# MCU.net
KiCad netlist of a schematic drawn in Altium Designer
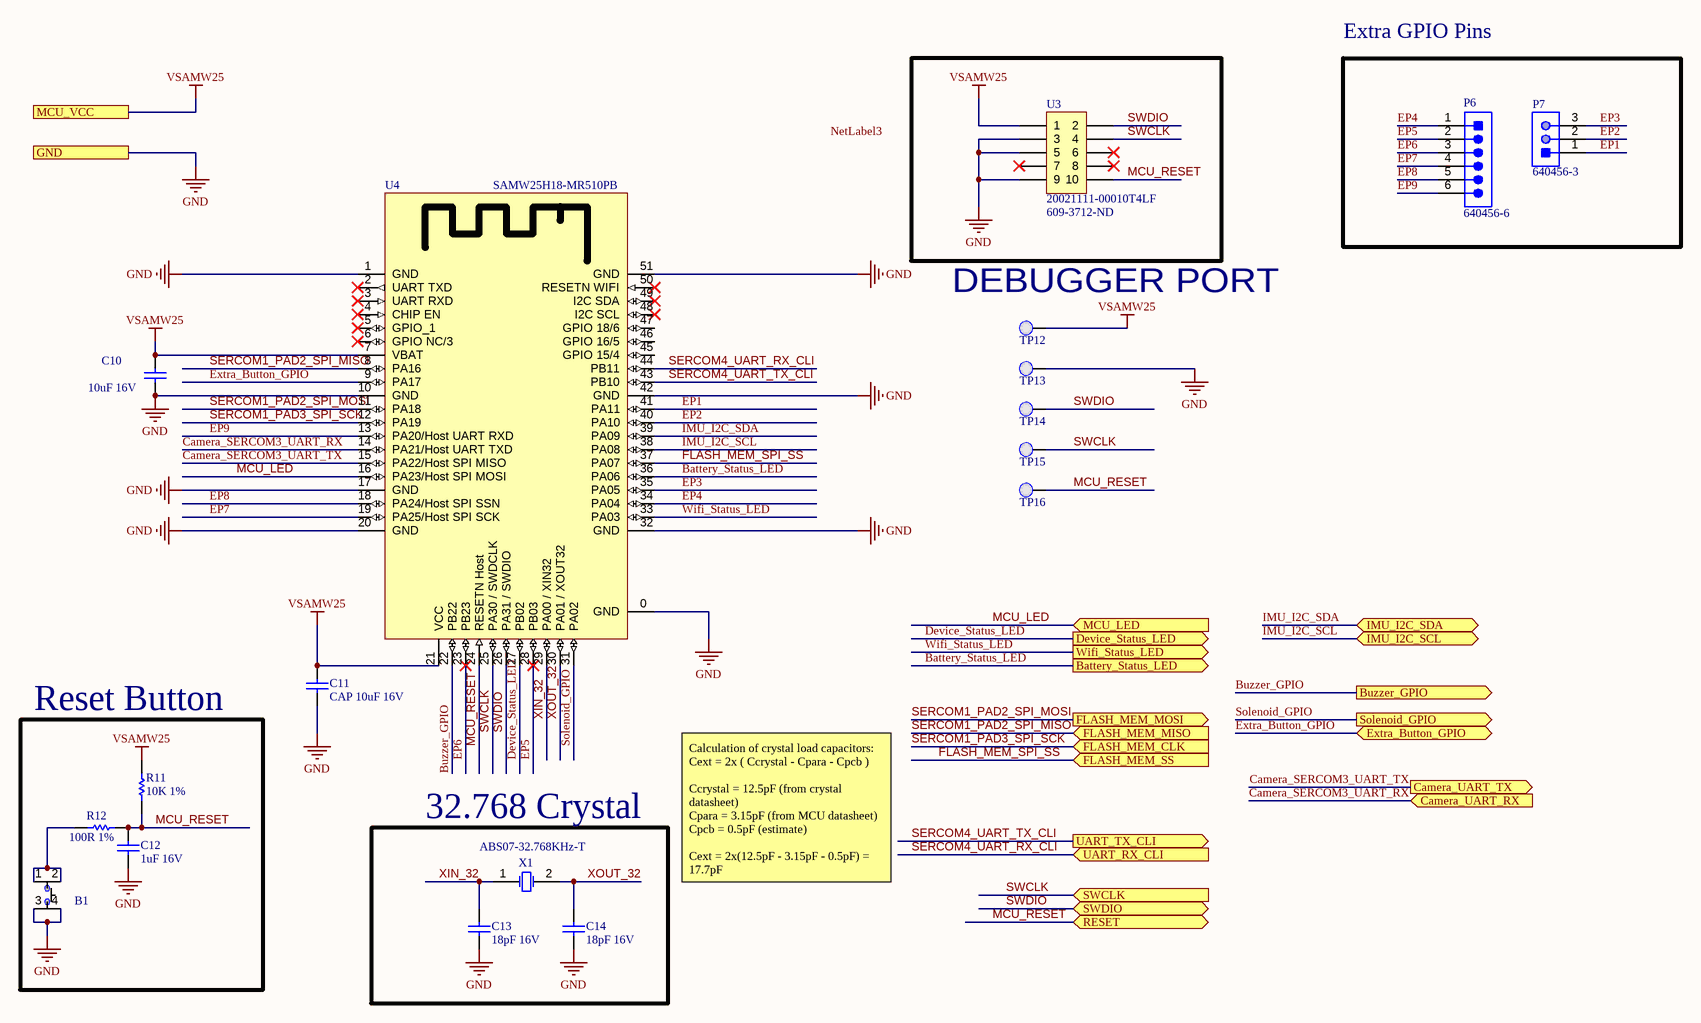
[diagram p0: MCU.SchDoc]

(export (version "E")
  (design (tool "Eeschema 10.0.6"))
  (components
    (comp (ref "B1")
      (value "PTS810 SJK 250 SMTR LFS")
      (footprint "PTS810 SJK 250 SMTR LFS")
      (description "SWITCH TACTILE SPST-NO 0.05A 16V Tactile Switch SPST-NO Top Actuated Surface Mount")
      (fields
        (field (name "MANUFACTURER") "ITT /  C&K Components")
        (field (name "MANUFACTURER PART NUMBER") "PTS810SJK250SMTRLFS")
      )
      (libsource (lib "Schematics") (part "PTS810 SJK 250 SMTR LFS"))
    )
    (comp (ref "C10")
      (value "10uF 16V")
      (footprint "CAPC0805(2012)145_N")
      (description "CAP 10uF 16V ±10% 0805 (2012 Metric) Thickness 1.45mm SMD")
      (fields (field (name "TOLERANCE") "Â±10%"))
      (libsource (lib "Altium Content Vault") (part "CAP"))
    )
    (comp (ref "C11")
      (value "CAP 10uF 16V")
      (footprint "CAPC0805(2012)145_N")
      (description "CAP 10uF 16V ±10% 0805 (2012 Metric) Thickness 1.45mm SMD")
      (fields (field (name "TOLERANCE") "Â±10%"))
      (libsource (lib "Altium Content Vault") (part "CAP"))
    )
    (comp (ref "C12")
      (value "1uF 16V")
      (footprint "CAPC0603(1608)100_N")
      (description "CAP 1uF 16V ±5% 0603 (1608 Metric) Thickness 1mm SMD")
      (fields (field (name "TOLERANCE") "Â±5%"))
      (libsource (lib "Altium Content Vault") (part "CAP"))
    )
    (comp (ref "C13")
      (value "18pF 16V")
      (footprint "CAPC0603(1608)100_N")
      (description "CAP 18pF 16V ±5% 0603 (1608 Metric) Thickness 1mm SMD")
      (fields (field (name "TOLERANCE") "Â±5%"))
      (libsource (lib "Altium Content Vault") (part "CAP"))
    )
    (comp (ref "C14")
      (value "18pF 16V")
      (footprint "CAPC0603(1608)100_N")
      (description "CAP 18pF 16V ±5% 0603 (1608 Metric) Thickness 1mm SMD")
      (fields (field (name "TOLERANCE") "Â±5%"))
      (libsource (lib "Altium Content Vault") (part "CAP"))
    )
    (comp (ref "P6")
      (value "640456-6")
      (footprint "TECO-640456-6_V")
      (fields (field (name "MANUFACTURER") "TE Connectivity"))
      (libsource (lib "Altium Content Vault") (part "CN-1P-M-R6"))
    )
    (comp (ref "P7")
      (value "640456-3")
      (footprint "TECO-640456-3")
      (description "Male Header, Pitch 2.54 mm, 1 x 3 Position, Height 10.03 mm, Tail Length 3.56 mm, -55 to 105 degC")
      (fields (field (name "MANUFACTURER") "TE Connectivity"))
      (libsource (lib "Altium Content Vault") (part "CN-1P-M-R3"))
    )
    (comp (ref "R11")
      (value "10K 1%")
      (footprint "RESC0603(1608)_N")
      (description "10K 0.1W 1% 0603 (1608 Metric)  SMD")
      (fields (field (name "POWER") "0.1 W") (field (name "TOLERANCE") "1 %"))
      (libsource (lib "Altium Content Vault") (part "RES"))
    )
    (comp (ref "R12")
      (value "100R 1%")
      (footprint "RESC0603(1608)_N")
      (description "100R 0.1W 1% 0603 (1608 Metric)  SMD")
      (fields (field (name "TOLERANCE") "1 %") (field (name "POWER") "0.1 W"))
      (libsource (lib "Altium Content Vault") (part "RES"))
    )
    (comp (ref "TP12")
      (value "0.1\" Pad")
      (footprint "PCBComponent")
      (libsource (lib "Components - 12.02.20 - 18.05") (part "0.1{dblquote} Pad-A.4"))
    )
    (comp (ref "TP13")
      (value "0.1\" Pad")
      (footprint "PCBComponent")
      (libsource (lib "Components - 12.02.20 - 18.05") (part "0.1{dblquote} Pad-A.4"))
    )
    (comp (ref "TP14")
      (value "0.1\" Pad")
      (footprint "PCBComponent")
      (libsource (lib "Components - 12.02.20 - 18.05") (part "0.1{dblquote} Pad-A.4"))
    )
    (comp (ref "TP15")
      (value "0.1\" Pad")
      (footprint "PCBComponent")
      (libsource (lib "Components - 12.02.20 - 18.05") (part "0.1{dblquote} Pad-A.4"))
    )
    (comp (ref "TP16")
      (value "0.1\" Pad")
      (footprint "PCBComponent")
      (libsource (lib "Components - 12.02.20 - 18.05") (part "0.1{dblquote} Pad-A.4"))
    )
    (comp (ref "U3")
      (value "20021111-00010T4LF")
      (footprint "20021111-00010T4LF")
      (description "CONN HEADER 10POS UNSHD VERT T/H")
      (fields
        (field (name "MANUFACTURER") "Amphenol / FCI")
        (field (name "SUPPLIER PART NUMBER 1") "609-3712-ND")
      )
      (libsource (lib "Schematics") (part "20021111-00010T4LF"))
    )
    (comp (ref "U4")
      (value "SAMW25H18-MR510PB")
      (footprint "SAMW25H18-MR510PB")
      (description "RF TXRX MODULE WIFI TRACE ANT")
      (fields
        (field (name "MANUFACTURER") "Atmel")
        (field (name "MANUFACTURER PART NUMBER") "ATSAMW25H18-MR510PB")
      )
      (libsource (lib "Schematics") (part "SAMW25H18-MR510PB"))
    )
    (comp (ref "X1")
      (value "ABS07-32.768KHz-T")
      (footprint "ABRA-ABS07-2_V")
      (description "Crystal, 32.768 kHz, 12.5 pF, -40 to 85 degC, SMD Low Profile 3.2 x 1.5 x 0.9 mm, Tape and Reel")
      (fields (field (name "MANUFACTURER") "Abracon"))
      (libsource (lib "Altium Content Vault") (part "ABRA-ABS07-2"))
    )
  )
  (nets
    (net (code "1") (name "/Battery_Status_LED") (class "Default")
      (node (ref "U4") (pin "36") (pinfunction "PA06_36") (pintype "bidirectional"))
    )
    (net (code "2") (name "/Buzzer_GPIO") (class "Default")
      (node (ref "U4") (pin "22") (pinfunction "PB22_22") (pintype "bidirectional"))
    )
    (net (code "3") (name "/Camera_SERCOM3_UART_RX") (class "Default")
      (node (ref "U4") (pin "14") (pinfunction "PA21/Host_UART_TXD_14") (pintype "bidirectional"))
    )
    (net (code "4") (name "/Camera_SERCOM3_UART_TX") (class "Default")
      (node (ref "U4") (pin "15") (pinfunction "PA22/Host_SPI_MISO_15") (pintype "bidirectional"))
    )
    (net (code "5") (name "/Device_Status_LED") (class "Default")
      (node (ref "U4") (pin "27") (pinfunction "PB02_27") (pintype "bidirectional"))
    )
    (net (code "6") (name "/EP1") (class "Default")
      (node (ref "P7") (pin "1") (pinfunction "1_1") (pintype "passive"))
      (node (ref "U4") (pin "41") (pinfunction "PA11_41") (pintype "bidirectional"))
    )
    (net (code "7") (name "/EP2") (class "Default")
      (node (ref "P7") (pin "2") (pinfunction "2_2") (pintype "passive"))
      (node (ref "U4") (pin "40") (pinfunction "PA10_40") (pintype "bidirectional"))
    )
    (net (code "8") (name "/EP3") (class "Default")
      (node (ref "P7") (pin "3") (pinfunction "3_3") (pintype "passive"))
      (node (ref "U4") (pin "35") (pinfunction "PA05_35") (pintype "bidirectional"))
    )
    (net (code "9") (name "/EP4") (class "Default")
      (node (ref "P6") (pin "1") (pinfunction "1_1") (pintype "passive"))
      (node (ref "U4") (pin "34") (pinfunction "PA04_34") (pintype "bidirectional"))
    )
    (net (code "10") (name "/EP5") (class "Default")
      (node (ref "P6") (pin "2") (pinfunction "2_2") (pintype "passive"))
      (node (ref "U4") (pin "28") (pinfunction "PB03_28") (pintype "bidirectional"))
    )
    (net (code "11") (name "/EP6") (class "Default")
      (node (ref "P6") (pin "3") (pinfunction "3_3") (pintype "passive"))
      (node (ref "U4") (pin "23") (pinfunction "PB23_23") (pintype "bidirectional"))
    )
    (net (code "12") (name "/EP7") (class "Default")
      (node (ref "P6") (pin "4") (pinfunction "4_4") (pintype "passive"))
      (node (ref "U4") (pin "19") (pinfunction "PA25/Host_SPI_SCK_19") (pintype "bidirectional"))
    )
    (net (code "13") (name "/EP8") (class "Default")
      (node (ref "P6") (pin "5") (pinfunction "5_5") (pintype "passive"))
      (node (ref "U4") (pin "18") (pinfunction "PA24/Host_SPI_SSN_18") (pintype "bidirectional"))
    )
    (net (code "14") (name "/EP9") (class "Default")
      (node (ref "P6") (pin "6") (pinfunction "6_6") (pintype "passive"))
      (node (ref "U4") (pin "13") (pinfunction "PA20/Host_UART_RXD_13") (pintype "bidirectional"))
    )
    (net (code "15") (name "/Extra_Button_GPIO") (class "Default")
      (node (ref "U4") (pin "9") (pinfunction "PA17_9") (pintype "bidirectional"))
    )
    (net (code "16") (name "/FLASH_MEM_SPI_SS") (class "Default")
      (node (ref "U4") (pin "37") (pinfunction "PA07_37") (pintype "bidirectional"))
    )
    (net (code "17") (name "/IMU_I2C_SCL") (class "Default")
      (node (ref "U4") (pin "38") (pinfunction "PA08_38") (pintype "bidirectional"))
    )
    (net (code "18") (name "/IMU_I2C_SDA") (class "Default")
      (node (ref "U4") (pin "39") (pinfunction "PA09_39") (pintype "bidirectional"))
    )
    (net (code "19") (name "/MCU_LED") (class "Default")
      (node (ref "U4") (pin "16") (pinfunction "PA23/Host_SPI_MOSI_16") (pintype "bidirectional"))
    )
    (net (code "20") (name "/MCU_RESET") (class "Default")
      (node (ref "C12") (pin "2") (pinfunction "2_2") (pintype "passive"))
      (node (ref "R11") (pin "1") (pinfunction "1_1") (pintype "passive"))
      (node (ref "R12") (pin "2") (pinfunction "2_2") (pintype "passive"))
      (node (ref "TP16") (pin "1") (pinfunction "PAD_1") (pintype "passive"))
      (node (ref "U3") (pin "10") (pinfunction "10_10") (pintype "passive"))
      (node (ref "U4") (pin "24") (pinfunction "RESETN_Host_24") (pintype "input"))
    )
    (net (code "22") (name "/SERCOM1_PAD2_SPI_MISO") (class "Default")
      (node (ref "U4") (pin "8") (pinfunction "PA16_8") (pintype "bidirectional"))
    )
    (net (code "23") (name "/SERCOM1_PAD2_SPI_MOSI") (class "Default")
      (node (ref "U4") (pin "11") (pinfunction "PA18_11") (pintype "bidirectional"))
    )
    (net (code "24") (name "/SERCOM1_PAD3_SPI_SCK") (class "Default")
      (node (ref "U4") (pin "12") (pinfunction "PA19_12") (pintype "bidirectional"))
    )
    (net (code "25") (name "/SERCOM4_UART_RX_CLI") (class "Default")
      (node (ref "U4") (pin "44") (pinfunction "PB11_44") (pintype "bidirectional"))
    )
    (net (code "26") (name "/SERCOM4_UART_TX_CLI") (class "Default")
      (node (ref "U4") (pin "43") (pinfunction "PB10_43") (pintype "bidirectional"))
    )
    (net (code "27") (name "/SWCLK") (class "Default")
      (node (ref "TP15") (pin "1") (pinfunction "PAD_1") (pintype "passive"))
      (node (ref "U3") (pin "4") (pinfunction "4_4") (pintype "passive"))
      (node (ref "U4") (pin "25") (pinfunction "PA30_/_SWDCLK_25") (pintype "bidirectional"))
    )
    (net (code "28") (name "/SWDIO") (class "Default")
      (node (ref "TP14") (pin "1") (pinfunction "PAD_1") (pintype "passive"))
      (node (ref "U3") (pin "2") (pinfunction "2_2") (pintype "passive"))
      (node (ref "U4") (pin "26") (pinfunction "PA31_/_SWDIO_26") (pintype "bidirectional"))
    )
    (net (code "29") (name "/Solenoid_GPIO") (class "Default")
      (node (ref "U4") (pin "31") (pinfunction "PA02_31") (pintype "bidirectional"))
    )
    (net (code "30") (name "/Wifi_Status_LED") (class "Default")
      (node (ref "U4") (pin "33") (pinfunction "PA03_33") (pintype "bidirectional"))
    )
    (net (code "31") (name "/XIN_32") (class "Default")
      (node (ref "C13") (pin "2") (pinfunction "2_2") (pintype "passive"))
      (node (ref "U4") (pin "29") (pinfunction "PA00_/_XIN32_29") (pintype "bidirectional"))
      (node (ref "X1") (pin "1") (pinfunction "X1_1") (pintype "passive"))
    )
    (net (code "32") (name "/XOUT_32") (class "Default")
      (node (ref "C14") (pin "2") (pinfunction "2_2") (pintype "passive"))
      (node (ref "U4") (pin "30") (pinfunction "PA01_/_XOUT32_30") (pintype "bidirectional"))
      (node (ref "X1") (pin "2") (pinfunction "X2_2") (pintype "passive"))
    )
    (net (code "33") (name "GND") (class "Default")
      (node (ref "B1") (pin "3") (pinfunction "3_3") (pintype "power_in"))
      (node (ref "B1") (pin "4") (pinfunction "4_4") (pintype "power_in"))
      (node (ref "C10") (pin "1") (pinfunction "1_1") (pintype "passive"))
      (node (ref "C11") (pin "1") (pinfunction "1_1") (pintype "passive"))
      (node (ref "C12") (pin "1") (pinfunction "1_1") (pintype "passive"))
      (node (ref "C13") (pin "1") (pinfunction "1_1") (pintype "passive"))
      (node (ref "C14") (pin "1") (pinfunction "1_1") (pintype "passive"))
      (node (ref "TP13") (pin "1") (pinfunction "PAD_1") (pintype "passive"))
      (node (ref "U3") (pin "3") (pinfunction "3_3") (pintype "passive"))
      (node (ref "U3") (pin "5") (pinfunction "5_5") (pintype "passive"))
      (node (ref "U3") (pin "9") (pinfunction "9_9") (pintype "passive"))
      (node (ref "U4") (pin "0") (pinfunction "GND_0") (pintype "power_in"))
      (node (ref "U4") (pin "1") (pinfunction "GND_1") (pintype "power_in"))
      (node (ref "U4") (pin "10") (pinfunction "GND_10") (pintype "power_in"))
      (node (ref "U4") (pin "17") (pinfunction "GND_17") (pintype "power_in"))
      (node (ref "U4") (pin "20") (pinfunction "GND_20") (pintype "power_in"))
      (node (ref "U4") (pin "32") (pinfunction "GND_32") (pintype "power_in"))
      (node (ref "U4") (pin "42") (pinfunction "GND_42") (pintype "power_in"))
      (node (ref "U4") (pin "51") (pinfunction "GND_51") (pintype "power_in"))
    )
    (net (code "34") (name "Net-(B1-Pad1)") (class "Default")
      (node (ref "B1") (pin "1") (pinfunction "1_1") (pintype "power_in"))
      (node (ref "B1") (pin "2") (pinfunction "2_2") (pintype "power_in"))
      (node (ref "R12") (pin "1") (pinfunction "1_1") (pintype "passive"))
    )
    (net (code "35") (name "VSAMW25") (class "Default")
      (node (ref "C10") (pin "2") (pinfunction "2_2") (pintype "passive"))
      (node (ref "C11") (pin "2") (pinfunction "2_2") (pintype "passive"))
      (node (ref "R11") (pin "2") (pinfunction "2_2") (pintype "passive"))
      (node (ref "TP12") (pin "1") (pinfunction "PAD_1") (pintype "passive"))
      (node (ref "U3") (pin "1") (pinfunction "1_1") (pintype "passive"))
      (node (ref "U4") (pin "21") (pinfunction "VCC_21") (pintype "power_in"))
      (node (ref "U4") (pin "7") (pinfunction "VBAT_7") (pintype "power_in"))
    )
    (net (code "36") (name "unconnected-(U3-Pad6)") (class "Default")
      (node (ref "U3") (pin "6") (pinfunction "6_6") (pintype "passive+no_connect"))
    )
    (net (code "37") (name "unconnected-(U3-Pad7)") (class "Default")
      (node (ref "U3") (pin "7") (pinfunction "7_7") (pintype "passive+no_connect"))
    )
    (net (code "38") (name "unconnected-(U3-Pad8)") (class "Default")
      (node (ref "U3") (pin "8") (pinfunction "8_8") (pintype "passive+no_connect"))
    )
    (net (code "39") (name "unconnected-(U4-CHIP_EN-Pad4)") (class "Default")
      (node (ref "U4") (pin "4") (pinfunction "CHIP_EN_4") (pintype "input+no_connect"))
    )
    (net (code "40") (name "unconnected-(U4-GPIO_1-Pad5)") (class "Default")
      (node (ref "U4") (pin "5") (pinfunction "GPIO_1_5") (pintype "bidirectional+no_connect"))
    )
    (net (code "41") (name "unconnected-(U4-GPIO_15{slash}4-Pad45)") (class "Default")
      (node (ref "U4") (pin "45") (pinfunction "GPIO_15/4_45") (pintype "bidirectional"))
    )
    (net (code "42") (name "unconnected-(U4-GPIO_16{slash}5-Pad46)") (class "Default")
      (node (ref "U4") (pin "46") (pinfunction "GPIO_16/5_46") (pintype "bidirectional"))
    )
    (net (code "43") (name "unconnected-(U4-GPIO_18{slash}6-Pad47)") (class "Default")
      (node (ref "U4") (pin "47") (pinfunction "GPIO_18/6_47") (pintype "bidirectional"))
    )
    (net (code "44") (name "unconnected-(U4-GPIO_NC{slash}3-Pad6)") (class "Default")
      (node (ref "U4") (pin "6") (pinfunction "GPIO_NC/3_6") (pintype "bidirectional+no_connect"))
    )
    (net (code "45") (name "unconnected-(U4-I2C_SCL-Pad48)") (class "Default")
      (node (ref "U4") (pin "48") (pinfunction "I2C_SCL_48") (pintype "bidirectional+no_connect"))
    )
    (net (code "46") (name "unconnected-(U4-I2C_SDA-Pad49)") (class "Default")
      (node (ref "U4") (pin "49") (pinfunction "I2C_SDA_49") (pintype "bidirectional+no_connect"))
    )
    (net (code "47") (name "unconnected-(U4-RESETN_WIFI-Pad50)") (class "Default")
      (node (ref "U4") (pin "50") (pinfunction "RESETN_WIFI_50") (pintype "input+no_connect"))
    )
    (net (code "48") (name "unconnected-(U4-UART_RXD-Pad3)") (class "Default")
      (node (ref "U4") (pin "3") (pinfunction "UART_RXD_3") (pintype "input+no_connect"))
    )
    (net (code "49") (name "unconnected-(U4-UART_TXD-Pad2)") (class "Default")
      (node (ref "U4") (pin "2") (pinfunction "UART_TXD_2") (pintype "output+no_connect"))
    )
  )
)
